# TelecarRemoteControlStc8051.net
KiCad netlist of a schematic drawn in Altium Designer
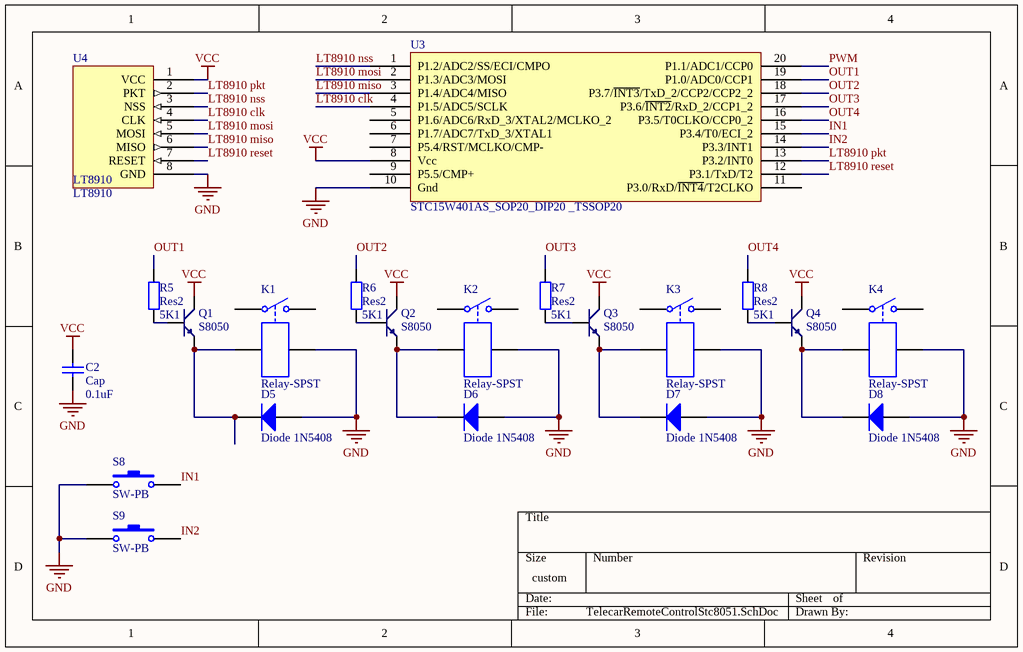
[diagram p0: TelecarRemoteControlStc8051.SchDoc]

(export (version "E")
  (design (tool "Eeschema 10.0.6"))
  (components
    (comp (ref "C2")
      (value "Cap")
      (footprint "RAD-0.3")
      (description "Capacitor")
      (fields (field (name "ALTIUM_VALUE") "0.1uF") (field (name "PUBLISHER") "Altium Limited"))
      (libsource (lib "Miscellaneous Devices") (part "Cap"))
    )
    (comp (ref "D5")
      (value "Diode 1N5408")
      (footprint "DIO18.84-9.6x5.6")
      (description "3 Amp Medium Power Silicon Rectifier Diode")
      (fields (field (name "PUBLISHER") "Altium Limited"))
      (libsource (lib "Miscellaneous Devices") (part "Diode 1N5408"))
    )
    (comp (ref "D6")
      (value "Diode 1N5408")
      (footprint "DIO18.84-9.6x5.6")
      (description "3 Amp Medium Power Silicon Rectifier Diode")
      (fields (field (name "PUBLISHER") "Altium Limited"))
      (libsource (lib "Miscellaneous Devices") (part "Diode 1N5408"))
    )
    (comp (ref "D7")
      (value "Diode 1N5408")
      (footprint "DIO18.84-9.6x5.6")
      (description "3 Amp Medium Power Silicon Rectifier Diode")
      (fields (field (name "PUBLISHER") "Altium Limited"))
      (libsource (lib "Miscellaneous Devices") (part "Diode 1N5408"))
    )
    (comp (ref "D8")
      (value "Diode 1N5408")
      (footprint "DIO18.84-9.6x5.6")
      (description "3 Amp Medium Power Silicon Rectifier Diode")
      (fields (field (name "PUBLISHER") "Altium Limited"))
      (libsource (lib "Miscellaneous Devices") (part "Diode 1N5408"))
    )
    (comp (ref "K1")
      (value "Relay-SPST")
      (footprint "DIP-P4")
      (description "Single-Pole Single-Throw Relay")
      (fields (field (name "PUBLISHER") "Altium Limited"))
      (libsource (lib "Miscellaneous Devices") (part "Relay-SPST"))
    )
    (comp (ref "K2")
      (value "Relay-SPST")
      (footprint "DIP-P4")
      (description "Single-Pole Single-Throw Relay")
      (fields (field (name "PUBLISHER") "Altium Limited"))
      (libsource (lib "Miscellaneous Devices") (part "Relay-SPST"))
    )
    (comp (ref "K3")
      (value "Relay-SPST")
      (footprint "DIP-P4")
      (description "Single-Pole Single-Throw Relay")
      (fields (field (name "PUBLISHER") "Altium Limited"))
      (libsource (lib "Miscellaneous Devices") (part "Relay-SPST"))
    )
    (comp (ref "K4")
      (value "Relay-SPST")
      (footprint "DIP-P4")
      (description "Single-Pole Single-Throw Relay")
      (fields (field (name "PUBLISHER") "Altium Limited"))
      (libsource (lib "Miscellaneous Devices") (part "Relay-SPST"))
    )
    (comp (ref "Q1")
      (value "S8050")
      (footprint "SOT-23R")
      (description "8050/BCW846/BCW847")
      (libsource (lib "战舰STM32开发板底板封装库") (part "NPN"))
    )
    (comp (ref "Q2")
      (value "S8050")
      (footprint "SOT-23R")
      (description "8050/BCW846/BCW847")
      (libsource (lib "战舰STM32开发板底板封装库") (part "NPN"))
    )
    (comp (ref "Q3")
      (value "S8050")
      (footprint "SOT-23R")
      (description "8050/BCW846/BCW847")
      (libsource (lib "战舰STM32开发板底板封装库") (part "NPN"))
    )
    (comp (ref "Q4")
      (value "S8050")
      (footprint "SOT-23R")
      (description "8050/BCW846/BCW847")
      (libsource (lib "战舰STM32开发板底板封装库") (part "NPN"))
    )
    (comp (ref "R5")
      (value "Res2")
      (footprint "AXIAL-0.4")
      (description "Resistor")
      (fields (field (name "ALTIUM_VALUE") "5K1") (field (name "PUBLISHER") "Altium Limited"))
      (libsource (lib "Miscellaneous Devices") (part "Res2"))
    )
    (comp (ref "R6")
      (value "Res2")
      (footprint "AXIAL-0.4")
      (description "Resistor")
      (fields (field (name "ALTIUM_VALUE") "5K1") (field (name "PUBLISHER") "Altium Limited"))
      (libsource (lib "Miscellaneous Devices") (part "Res2"))
    )
    (comp (ref "R7")
      (value "Res2")
      (footprint "AXIAL-0.4")
      (description "Resistor")
      (fields (field (name "ALTIUM_VALUE") "5K1") (field (name "PUBLISHER") "Altium Limited"))
      (libsource (lib "Miscellaneous Devices") (part "Res2"))
    )
    (comp (ref "R8")
      (value "Res2")
      (footprint "AXIAL-0.4")
      (description "Resistor")
      (fields (field (name "ALTIUM_VALUE") "5K1") (field (name "PUBLISHER") "Altium Limited"))
      (libsource (lib "Miscellaneous Devices") (part "Res2"))
    )
    (comp (ref "S8")
      (value "SW-PB")
      (footprint "SPST-2")
      (description "Switch")
      (fields (field (name "PUBLISHER") "Altium Limited"))
      (libsource (lib "Miscellaneous Devices") (part "SW-PB"))
    )
    (comp (ref "S9")
      (value "SW-PB")
      (footprint "SPST-2")
      (description "Switch")
      (fields (field (name "PUBLISHER") "Altium Limited"))
      (libsource (lib "Miscellaneous Devices") (part "SW-PB"))
    )
    (comp (ref "U3")
      (value "STC15W401AS_SOP20_DIP20 _TSSOP20")
      (footprint "TSSOP20")
      (libsource (lib "stcmcu_altium_lib") (part "STC15W401AS_SOP20_DIP20 _TSSOP20"))
    )
    (comp (ref "U4") (value "LT8910") (libsource (lib "glib") (part "LT8910")))
  )
  (nets
    (net (code "1") (name "/IN1") (class "Default")
      (node (ref "S8") (pin "2") (pinfunction "2_2") (pintype "passive"))
      (node (ref "U3") (pin "15") (pinfunction "P3.4/T0/ECI_2_15") (pintype "passive"))
    )
    (net (code "2") (name "/IN2") (class "Default")
      (node (ref "S9") (pin "2") (pinfunction "2_2") (pintype "passive"))
      (node (ref "U3") (pin "14") (pinfunction "P3.3/INT1_14") (pintype "passive"))
    )
    (net (code "3") (name "/LT8910 clk") (class "Default")
      (node (ref "U3") (pin "4") (pinfunction "P1.5/ADC5/SCLK_4") (pintype "passive"))
      (node (ref "U4") (pin "4") (pinfunction "CLK_4") (pintype "input"))
    )
    (net (code "4") (name "/LT8910 miso") (class "Default")
      (node (ref "U3") (pin "3") (pinfunction "P1.4/ADC4/MISO_3") (pintype "passive"))
      (node (ref "U4") (pin "6") (pinfunction "MISO_6") (pintype "output"))
    )
    (net (code "5") (name "/LT8910 mosi") (class "Default")
      (node (ref "U3") (pin "2") (pinfunction "P1.3/ADC3/MOSI_2") (pintype "passive"))
      (node (ref "U4") (pin "5") (pinfunction "MOSI_5") (pintype "input"))
    )
    (net (code "6") (name "/LT8910 nss") (class "Default")
      (node (ref "U3") (pin "1") (pinfunction "P1.2/ADC2/SS/ECI/CMPO_1") (pintype "passive"))
      (node (ref "U4") (pin "3") (pinfunction "NSS_3") (pintype "input"))
    )
    (net (code "7") (name "/LT8910 pkt") (class "Default")
      (node (ref "U3") (pin "13") (pinfunction "P3.2/INT0_13") (pintype "passive"))
      (node (ref "U4") (pin "2") (pinfunction "PKT_2") (pintype "output"))
    )
    (net (code "8") (name "/LT8910 reset") (class "Default")
      (node (ref "U3") (pin "12") (pinfunction "P3.1/TxD/T2_12") (pintype "passive"))
      (node (ref "U4") (pin "7") (pinfunction "RESET_7") (pintype "input"))
    )
    (net (code "9") (name "/OUT1") (class "Default")
      (node (ref "R5") (pin "2") (pinfunction "2_2") (pintype "passive"))
      (node (ref "U3") (pin "19") (pinfunction "P1.0/ADC0/CCP1_19") (pintype "passive"))
    )
    (net (code "10") (name "/OUT2") (class "Default")
      (node (ref "R6") (pin "2") (pinfunction "2_2") (pintype "passive"))
      (node (ref "U3") (pin "18") (pinfunction "P3.7/~{INT3}/TxD_2/CCP2/CCP2_2_18") (pintype "passive"))
    )
    (net (code "11") (name "/OUT3") (class "Default")
      (node (ref "R7") (pin "2") (pinfunction "2_2") (pintype "passive"))
      (node (ref "U3") (pin "17") (pinfunction "P3.6/~{INT2}/RxD_2/CCP1_2_17") (pintype "passive"))
    )
    (net (code "12") (name "/OUT4") (class "Default")
      (node (ref "R8") (pin "2") (pinfunction "2_2") (pintype "passive"))
      (node (ref "U3") (pin "16") (pinfunction "P3.5/T0CLKO/CCP0_2_16") (pintype "passive"))
    )
    (net (code "13") (name "/PWM") (class "Default")
      (node (ref "U3") (pin "20") (pinfunction "P1.1/ADC1/CCP0_20") (pintype "passive"))
    )
    (net (code "14") (name "GND") (class "Default")
      (node (ref "C2") (pin "1") (pinfunction "1_1") (pintype "passive"))
      (node (ref "D5") (pin "1") (pinfunction "A_1") (pintype "passive"))
      (node (ref "D6") (pin "1") (pinfunction "A_1") (pintype "passive"))
      (node (ref "D7") (pin "1") (pinfunction "A_1") (pintype "passive"))
      (node (ref "D8") (pin "1") (pinfunction "A_1") (pintype "passive"))
      (node (ref "K1") (pin "4") (pinfunction "4_4") (pintype "passive"))
      (node (ref "K2") (pin "4") (pinfunction "4_4") (pintype "passive"))
      (node (ref "K3") (pin "4") (pinfunction "4_4") (pintype "passive"))
      (node (ref "K4") (pin "4") (pinfunction "4_4") (pintype "passive"))
      (node (ref "S8") (pin "1") (pinfunction "1_1") (pintype "passive"))
      (node (ref "S9") (pin "1") (pinfunction "1_1") (pintype "passive"))
      (node (ref "U3") (pin "10") (pinfunction "Gnd_10") (pintype "passive"))
      (node (ref "U4") (pin "8") (pinfunction "GND_8") (pintype "power_in"))
    )
    (net (code "15") (name "Net-(D5-K)") (class "Default")
      (node (ref "D5") (pin "2") (pinfunction "K_2") (pintype "passive"))
      (node (ref "K1") (pin "3") (pinfunction "3_3") (pintype "passive"))
      (node (ref "Q1") (pin "1") (pinfunction "E_1") (pintype "passive"))
    )
    (net (code "16") (name "Net-(D6-K)") (class "Default")
      (node (ref "D6") (pin "2") (pinfunction "K_2") (pintype "passive"))
      (node (ref "K2") (pin "3") (pinfunction "3_3") (pintype "passive"))
      (node (ref "Q2") (pin "1") (pinfunction "E_1") (pintype "passive"))
    )
    (net (code "17") (name "Net-(D7-K)") (class "Default")
      (node (ref "D7") (pin "2") (pinfunction "K_2") (pintype "passive"))
      (node (ref "K3") (pin "3") (pinfunction "3_3") (pintype "passive"))
      (node (ref "Q3") (pin "1") (pinfunction "E_1") (pintype "passive"))
    )
    (net (code "18") (name "Net-(D8-K)") (class "Default")
      (node (ref "D8") (pin "2") (pinfunction "K_2") (pintype "passive"))
      (node (ref "K4") (pin "3") (pinfunction "3_3") (pintype "passive"))
      (node (ref "Q4") (pin "1") (pinfunction "E_1") (pintype "passive"))
    )
    (net (code "19") (name "Net-(Q1-B)") (class "Default")
      (node (ref "Q1") (pin "2") (pinfunction "B_2") (pintype "passive"))
      (node (ref "R5") (pin "1") (pinfunction "1_1") (pintype "passive"))
    )
    (net (code "20") (name "Net-(Q2-B)") (class "Default")
      (node (ref "Q2") (pin "2") (pinfunction "B_2") (pintype "passive"))
      (node (ref "R6") (pin "1") (pinfunction "1_1") (pintype "passive"))
    )
    (net (code "21") (name "Net-(Q3-B)") (class "Default")
      (node (ref "Q3") (pin "2") (pinfunction "B_2") (pintype "passive"))
      (node (ref "R7") (pin "1") (pinfunction "1_1") (pintype "passive"))
    )
    (net (code "22") (name "Net-(Q4-B)") (class "Default")
      (node (ref "Q4") (pin "2") (pinfunction "B_2") (pintype "passive"))
      (node (ref "R8") (pin "1") (pinfunction "1_1") (pintype "passive"))
    )
    (net (code "23") (name "VCC") (class "Default")
      (node (ref "C2") (pin "2") (pinfunction "2_2") (pintype "passive"))
      (node (ref "Q1") (pin "3") (pinfunction "C_3") (pintype "passive"))
      (node (ref "Q2") (pin "3") (pinfunction "C_3") (pintype "passive"))
      (node (ref "Q3") (pin "3") (pinfunction "C_3") (pintype "passive"))
      (node (ref "Q4") (pin "3") (pinfunction "C_3") (pintype "passive"))
      (node (ref "U3") (pin "8") (pinfunction "Vcc_8") (pintype "passive"))
      (node (ref "U4") (pin "1") (pinfunction "VCC_1") (pintype "power_in"))
    )
    (net (code "24") (name "unconnected-(K1-Pad1)") (class "Default")
      (node (ref "K1") (pin "1") (pinfunction "1_1") (pintype "passive"))
    )
    (net (code "25") (name "unconnected-(K1-Pad2)") (class "Default")
      (node (ref "K1") (pin "2") (pinfunction "2_2") (pintype "passive"))
    )
    (net (code "26") (name "unconnected-(K2-Pad1)") (class "Default")
      (node (ref "K2") (pin "1") (pinfunction "1_1") (pintype "passive"))
    )
    (net (code "27") (name "unconnected-(K2-Pad2)") (class "Default")
      (node (ref "K2") (pin "2") (pinfunction "2_2") (pintype "passive"))
    )
    (net (code "28") (name "unconnected-(K3-Pad1)") (class "Default")
      (node (ref "K3") (pin "1") (pinfunction "1_1") (pintype "passive"))
    )
    (net (code "29") (name "unconnected-(K3-Pad2)") (class "Default")
      (node (ref "K3") (pin "2") (pinfunction "2_2") (pintype "passive"))
    )
    (net (code "30") (name "unconnected-(K4-Pad1)") (class "Default")
      (node (ref "K4") (pin "1") (pinfunction "1_1") (pintype "passive"))
    )
    (net (code "31") (name "unconnected-(K4-Pad2)") (class "Default")
      (node (ref "K4") (pin "2") (pinfunction "2_2") (pintype "passive"))
    )
    (net (code "32") (name "unconnected-(U3-P1.6{slash}ADC6{slash}RxD_3{slash}XTAL2{slash}MCLKO_2-Pad5)") (class "Default")
      (node (ref "U3") (pin "5") (pinfunction "P1.6/ADC6/RxD_3/XTAL2/MCLKO_2_5") (pintype "passive"))
    )
    (net (code "33") (name "unconnected-(U3-P1.7{slash}ADC7{slash}TxD_3{slash}XTAL1-Pad6)") (class "Default")
      (node (ref "U3") (pin "6") (pinfunction "P1.7/ADC7/TxD_3/XTAL1_6") (pintype "passive"))
    )
    (net (code "34") (name "unconnected-(U3-P3.0{slash}RxD{slash}~{INT4}{slash}T2CLKO-Pad11)") (class "Default")
      (node (ref "U3") (pin "11") (pinfunction "P3.0/RxD/~{INT4}/T2CLKO_11") (pintype "passive"))
    )
    (net (code "35") (name "unconnected-(U3-P5.4{slash}RST{slash}MCLKO{slash}CMP--Pad7)") (class "Default")
      (node (ref "U3") (pin "7") (pinfunction "P5.4/RST/MCLKO/CMP-_7") (pintype "passive"))
    )
    (net (code "36") (name "unconnected-(U3-P5.5{slash}CMP+-Pad9)") (class "Default")
      (node (ref "U3") (pin "9") (pinfunction "P5.5/CMP+_9") (pintype "passive"))
    )
  )
)
